# Regulator3V3.net
KiCad netlist of a schematic drawn in Altium Designer
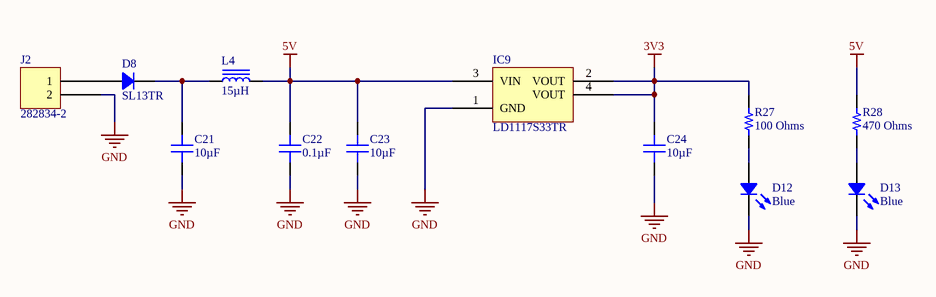
[diagram p0: Regulator3V3.SchDoc]

(export (version "E")
  (design (tool "Eeschema 10.0.6"))
  (components
    (comp (ref "C21")
      (value "10µF")
      (footprint "CAP 1206_3216 - 1.8MM")
      (description "CAP CER 10UF 10V X5R 1206")
      (fields
        (field (name "PART NUMBER") "CL31A106KPHNNNE")
        (field (name "MANUFACTURER") "Samsung Electro-Mechanics")
      )
      (libsource (lib "Celestial Altium Library - altium_library") (part "Capacitor"))
    )
    (comp (ref "C22")
      (value "0.1µF")
      (footprint "CAP 0603_1608")
      (description "CAP CER 0.1UF 16V X7R 0603")
      (fields (field (name "PART NUMBER") "CS0603KRX7R7BB104") (field (name "MANUFACTURER") "Yageo"))
      (libsource (lib "Celestial Altium Library - altium_library") (part "Capacitor"))
    )
    (comp (ref "C23")
      (value "10µF")
      (footprint "CAP 1206_3216 - 1.8MM")
      (description "CAP CER 10UF 10V X5R 1206")
      (fields
        (field (name "PART NUMBER") "CL31A106KPHNNNE")
        (field (name "MANUFACTURER") "Samsung Electro-Mechanics")
      )
      (libsource (lib "Celestial Altium Library - altium_library") (part "Capacitor"))
    )
    (comp (ref "C24")
      (value "10µF")
      (footprint "CAP 1206_3216 - 1.8MM")
      (description "CAP CER 10UF 10V X5R 1206")
      (fields
        (field (name "PART NUMBER") "CL31A106KPHNNNE")
        (field (name "MANUFACTURER") "Samsung Electro-Mechanics")
      )
      (libsource (lib "Celestial Altium Library - altium_library") (part "Capacitor"))
    )
    (comp (ref "D8")
      (value "SL13TR")
      (footprint "DO214AC SMA")
      (description "DIODE SCHOTTKY 30V 1A SMA")
      (fields (field (name "MANUFACTURER") "SMC Diode Solutions"))
      (libsource (lib "Celestial Altium Library - altium_library") (part "Diode"))
    )
    (comp (ref "D12")
      (value "Blue")
      (footprint "LED 0603_1608 BLUE")
      (description "LED BLUE CLEAR 2SMD")
      (fields
        (field (name "PART NUMBER") "EAST16084BA8")
        (field (name "MANUFACTURER") "Everlight Electronics Co Ltd")
      )
      (libsource (lib "Celestial Altium Library - altium_library") (part "LED"))
    )
    (comp (ref "D13")
      (value "Blue")
      (footprint "LED 0603_1608 BLUE")
      (description "LED BLUE CLEAR 2SMD")
      (fields
        (field (name "PART NUMBER") "EAST16084BA8")
        (field (name "MANUFACTURER") "Everlight Electronics Co Ltd")
      )
      (libsource (lib "Celestial Altium Library - altium_library") (part "LED"))
    )
    (comp (ref "IC9")
      (value "LD1117S33TR")
      (footprint "ST SOT-223")
      (description "IC REG LINEAR 3.3V 800MA SOT223")
      (fields (field (name "MANUFACTURER") "STMicroelectronics"))
      (libsource (lib "Celestial Altium Library - altium_library") (part "ST LD1117"))
    )
    (comp (ref "J2")
      (value "282834-2")
      (footprint "TE 282834-2")
      (description "TERM BLK 2P SIDE ENT 2.54MM PCB")
      (fields (field (name "MANUFACTURER") "TE Connectivity AMP Connectors") (field (name "VOLTAGE") "150V"))
      (libsource (lib "Celestial Altium Library - altium_library") (part "2 Pin"))
    )
    (comp (ref "L4")
      (value "15µH")
      (footprint "TDK VLCF4024-2")
      (description "FIXED IND 15UH 800MA 198 MOHM")
      (fields
        (field (name "PART NUMBER") "VLCF4024T-150MR80-2")
        (field (name "MANUFACTURER") "TDK Corporation")
      )
      (libsource (lib "Celestial Altium Library - altium_library") (part "Inductor"))
    )
    (comp (ref "R27")
      (value "100 Ohms")
      (footprint "RES 0603_1608")
      (description "RES SMD 100 OHM 1% 1/10W 0603")
      (fields
        (field (name "PART NUMBER") "ERJ-3EKF1000V")
        (field (name "MANUFACTURER") "Panasonic Electronic Components")
      )
      (libsource (lib "Celestial Altium Library - altium_library") (part "Resistor"))
    )
    (comp (ref "R28")
      (value "470 Ohms")
      (footprint "RES 0603_1608")
      (description "RES SMD 470 OHM 1% 1/10W 0603")
      (fields
        (field (name "PART NUMBER") "ERJ-3EKF4700V")
        (field (name "MANUFACTURER") "Panasonic Electronic Components")
      )
      (libsource (lib "Celestial Altium Library - altium_library") (part "Resistor"))
    )
  )
  (nets
    (net (code "1") (name "3V3") (class "Default")
      (node (ref "C24") (pin "2") (pinfunction "2_2") (pintype "passive"))
      (node (ref "IC9") (pin "2") (pinfunction "VOUT_2") (pintype "passive"))
      (node (ref "IC9") (pin "4") (pinfunction "VOUT_4") (pintype "passive"))
      (node (ref "R27") (pin "2") (pinfunction "2_2") (pintype "passive"))
    )
    (net (code "2") (name "5V") (class "Default")
      (node (ref "C22") (pin "2") (pinfunction "2_2") (pintype "passive"))
      (node (ref "C23") (pin "2") (pinfunction "2_2") (pintype "passive"))
      (node (ref "IC9") (pin "3") (pinfunction "VIN_3") (pintype "passive"))
      (node (ref "L4") (pin "2") (pinfunction "2_2") (pintype "passive"))
      (node (ref "R28") (pin "2") (pinfunction "2_2") (pintype "passive"))
    )
    (net (code "3") (name "GND") (class "Default")
      (node (ref "C21") (pin "1") (pinfunction "1_1") (pintype "passive"))
      (node (ref "C22") (pin "1") (pinfunction "1_1") (pintype "passive"))
      (node (ref "C23") (pin "1") (pinfunction "1_1") (pintype "passive"))
      (node (ref "C24") (pin "1") (pinfunction "1_1") (pintype "passive"))
      (node (ref "D12") (pin "2") (pinfunction "2_2") (pintype "passive"))
      (node (ref "D13") (pin "2") (pinfunction "2_2") (pintype "passive"))
      (node (ref "IC9") (pin "1") (pinfunction "GND_1") (pintype "passive"))
      (node (ref "J2") (pin "2") (pinfunction "2_2") (pintype "passive"))
    )
    (net (code "4") (name "Net-(C21-Pad2)") (class "Default")
      (node (ref "C21") (pin "2") (pinfunction "2_2") (pintype "passive"))
      (node (ref "D8") (pin "2") (pinfunction "2_2") (pintype "passive"))
      (node (ref "L4") (pin "1") (pinfunction "1_1") (pintype "passive"))
    )
    (net (code "5") (name "Net-(D8-Pad1)") (class "Default")
      (node (ref "D8") (pin "1") (pinfunction "1_1") (pintype "passive"))
      (node (ref "J2") (pin "1") (pinfunction "1_1") (pintype "passive"))
    )
    (net (code "6") (name "Net-(D12-Pad1)") (class "Default")
      (node (ref "D12") (pin "1") (pinfunction "1_1") (pintype "passive"))
      (node (ref "R27") (pin "1") (pinfunction "1_1") (pintype "passive"))
    )
    (net (code "7") (name "Net-(D13-Pad1)") (class "Default")
      (node (ref "D13") (pin "1") (pinfunction "1_1") (pintype "passive"))
      (node (ref "R28") (pin "1") (pinfunction "1_1") (pintype "passive"))
    )
  )
)
